# design.net
KiCad netlist of a schematic drawn in Altium Designer
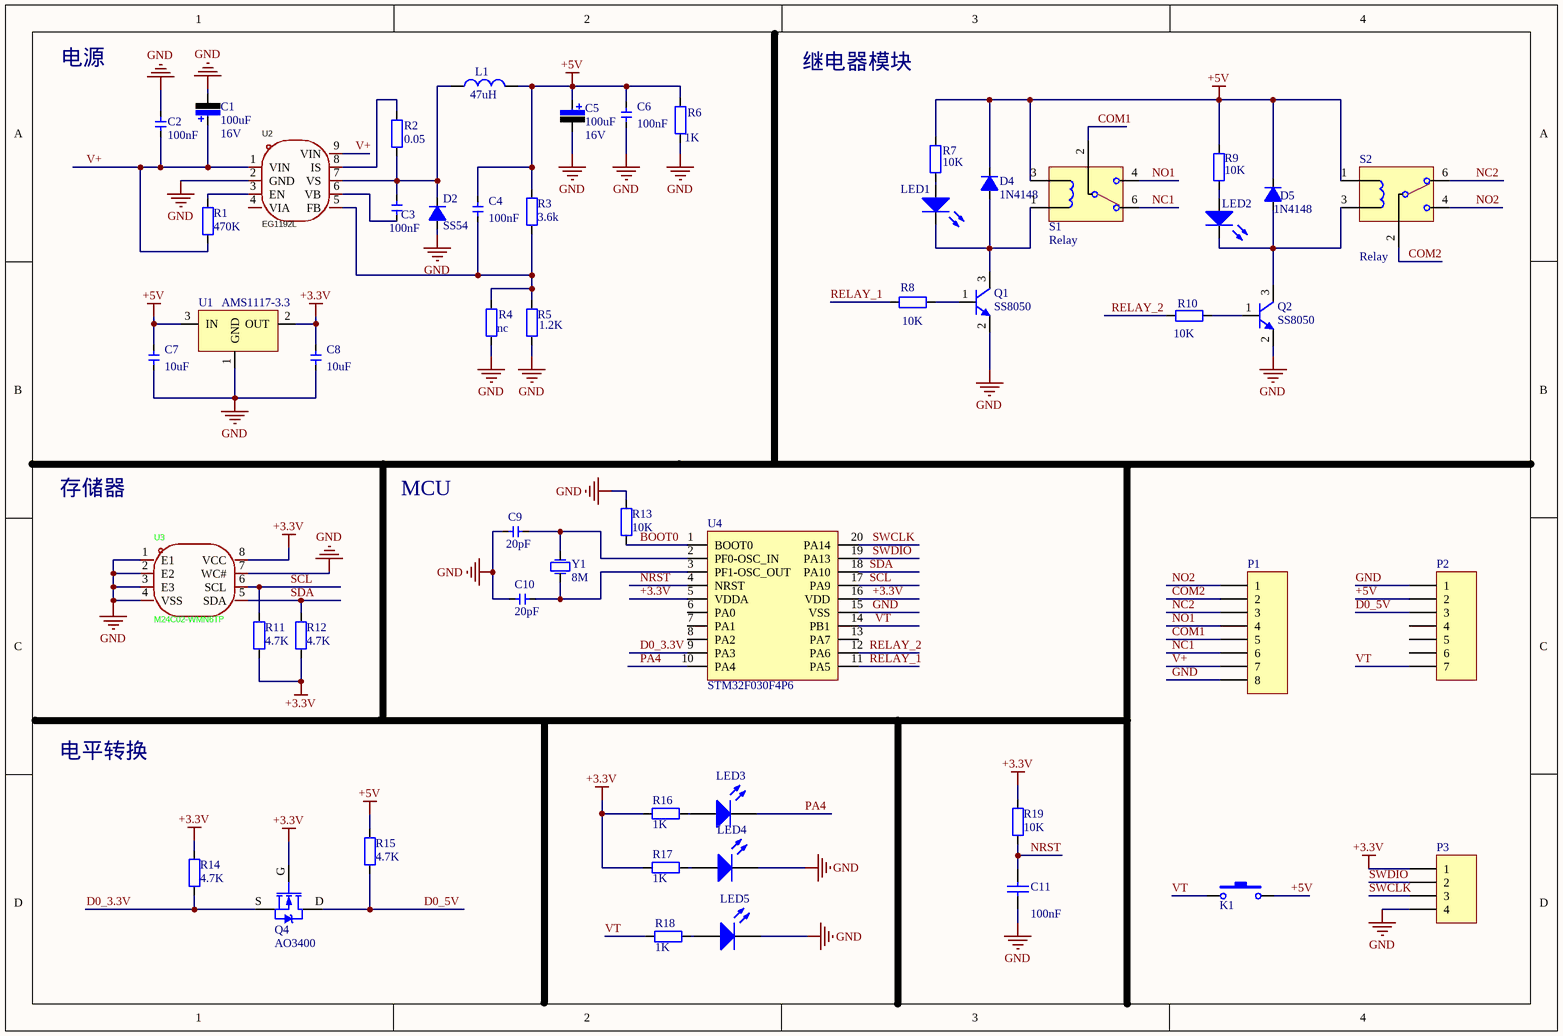
[diagram p0: 遥控启停.SchDoc]

(export (version "E")
  (design (tool "Eeschema 10.0.6"))
  (components
    (comp (ref "C1")
      (value "100uF")
      (footprint "16V100uF")
      (description "极性电解电容")
      (fields
        (field (name "VOL") "16V")
        (field (name "Comment") "Cap Pol")
        (field (name "PUBLISHER") "Altium Limited")
      )
      (libsource (lib "") (part "Cap Pol_1"))
    )
    (comp (ref "C2")
      (value "100nF")
      (footprint "C0603")
      (description "无极性电容")
      (fields (field (name "PUBLISHER") "Altium Limited"))
      (libsource (lib "Arrowy_Racing") (part "Cap"))
    )
    (comp (ref "C3")
      (value "100nF")
      (footprint "C0603")
      (description "无极性电容")
      (fields (field (name "PUBLISHER") "Altium Limited"))
      (libsource (lib "Arrowy_Racing") (part "Cap"))
    )
    (comp (ref "C4")
      (value "100nF")
      (footprint "C0603")
      (description "无极性电容")
      (fields (field (name "PUBLISHER") "Altium Limited"))
      (libsource (lib "Arrowy_Racing") (part "Cap"))
    )
    (comp (ref "C5")
      (value "100uF")
      (footprint "16V100uF")
      (description "极性电解电容")
      (fields
        (field (name "VOL") "16V")
        (field (name "Comment") "Cap Pol")
        (field (name "PUBLISHER") "Altium Limited")
      )
      (libsource (lib "Arrowy_Racing") (part "Cap Pol"))
    )
    (comp (ref "C6")
      (value "100nF")
      (footprint "C0603")
      (description "无极性电容")
      (fields (field (name "PUBLISHER") "Altium Limited"))
      (libsource (lib "Arrowy_Racing") (part "Cap"))
    )
    (comp (ref "C7")
      (value "10uF")
      (footprint "C0603")
      (description "无极性电容")
      (fields (field (name "PUBLISHER") "Altium Limited"))
      (libsource (lib "Arrowy_Racing") (part "Cap"))
    )
    (comp (ref "C8")
      (value "10uF")
      (footprint "C0603")
      (description "无极性电容")
      (fields (field (name "PUBLISHER") "Altium Limited"))
      (libsource (lib "Arrowy_Racing") (part "Cap"))
    )
    (comp (ref "C9")
      (value "20pF")
      (footprint "C0603")
      (description "无极性电容")
      (fields (field (name "PUBLISHER") "Altium Limited"))
      (libsource (lib "Arrowy_Racing") (part "Cap"))
    )
    (comp (ref "C10")
      (value "20pF")
      (footprint "C0603")
      (description "无极性电容")
      (fields (field (name "PUBLISHER") "Altium Limited"))
      (libsource (lib "Arrowy_Racing") (part "Cap"))
    )
    (comp (ref "C11")
      (value "100nF")
      (footprint "C0603")
      (description "Capacitor")
      (fields (field (name "Comment") "0.1uF") (field (name "PUBLISHER") "Altium Limited"))
      (libsource (lib "Miscellaneous Devices") (part "Cap"))
    )
    (comp (ref "D2")
      (value "SS54")
      (footprint "DIODE-SMA")
      (description "二极管")
      (libsource (lib "Arrowy_Racing") (part "Diode"))
    )
    (comp (ref "D4")
      (value "1N4148")
      (footprint "DIODE-1206")
      (description "二极管")
      (libsource (lib "Arrowy_Racing") (part "Diode"))
    )
    (comp (ref "D5")
      (value "1N4148")
      (footprint "DIODE-1206")
      (description "二极管")
      (libsource (lib "Arrowy_Racing") (part "Diode"))
    )
    (comp (ref "K1")
      (value "SW-PB")
      (footprint "SW-SMD_4P-L6.0-W6.0")
      (description "微动开关")
      (fields (field (name "SUPPLITER PART") "C961737") (field (name "PUBLISHER") "Altium Limited"))
      (libsource (lib "Arrowy_Racing") (part "SW-PB"))
    )
    (comp (ref "L1")
      (value "47uH")
      (footprint "IND-SMD_L4.5-W4.0")
      (description "电感")
      (fields (field (name "PUBLISHER") "Altium Limited"))
      (libsource (lib "Arrowy_Racing") (part "Inductor"))
    )
    (comp (ref "LED1")
      (value "LED")
      (footprint "LED0603-RD_RED")
      (description "发光二极管")
      (fields (field (name "PUBLISHER") "Altium Limited"))
      (libsource (lib "Arrowy_Racing") (part "LED"))
    )
    (comp (ref "LED2")
      (value "LED")
      (footprint "LED0603-RD_RED")
      (description "发光二极管")
      (fields (field (name "PUBLISHER") "Altium Limited"))
      (libsource (lib "Arrowy_Racing") (part "LED"))
    )
    (comp (ref "LED3")
      (value "LED0")
      (footprint "LED0603-RD_RED")
      (description "Typical INFRARED GaAs LED")
      (fields (field (name "PUBLISHER") "Altium Limited"))
      (libsource (lib "Miscellaneous Devices") (part "LED0"))
    )
    (comp (ref "LED4")
      (value "LED0")
      (footprint "LED0603-RD_RED")
      (description "Typical INFRARED GaAs LED")
      (fields (field (name "PUBLISHER") "Altium Limited"))
      (libsource (lib "Miscellaneous Devices") (part "LED0"))
    )
    (comp (ref "LED5")
      (value "LED0")
      (footprint "LED0603-RD_RED")
      (description "Typical INFRARED GaAs LED")
      (fields (field (name "PUBLISHER") "Altium Limited"))
      (libsource (lib "Miscellaneous Devices") (part "LED0"))
    )
    (comp (ref "P1")
      (value "Header 8")
      (footprint "XH2.54-W-8P")
      (description "Header, 8-Pin")
      (fields (field (name "PUBLISHER") "Altium Limited"))
      (libsource (lib "Miscellaneous Connectors") (part "Header 8"))
    )
    (comp (ref "P2")
      (value "Header 7")
      (footprint "HDR1X7")
      (description "Header, 7-Pin")
      (fields (field (name "PUBLISHER") "Altium Limited"))
      (libsource (lib "Miscellaneous Connectors") (part "Header 7"))
    )
    (comp (ref "P3")
      (value "Header 4")
      (footprint "HDR1X4")
      (description "Header, 4-Pin")
      (fields (field (name "PUBLISHER") "Altium Limited"))
      (libsource (lib "Miscellaneous Connectors") (part "Header 4"))
    )
    (comp (ref "Q1")
      (value "SS8050")
      (footprint "SOT-23")
      (description "NPN贴片三极管")
      (fields (field (name "PUBLISHER") "Altium Limited"))
      (libsource (lib "Arrowy_Racing") (part "SS8050"))
    )
    (comp (ref "Q2")
      (value "SS8050")
      (footprint "SOT-23")
      (description "NPN贴片三极管")
      (fields (field (name "PUBLISHER") "Altium Limited"))
      (libsource (lib "Arrowy_Racing") (part "SS8050"))
    )
    (comp (ref "Q4")
      (value "AO3400")
      (footprint "SOT-23-MOSFET")
      (description "N沟道MOS管")
      (libsource (lib "Arrowy_Racing") (part "MOSFET-N"))
    )
    (comp (ref "R1")
      (value "470K")
      (footprint "R0603")
      (description "贴片电阻")
      (fields (field (name "PUBLISHER") "Altium Limited"))
      (libsource (lib "Arrowy_Racing") (part "Res"))
    )
    (comp (ref "R2")
      (value "0.05")
      (footprint "R0603")
      (description "贴片电阻")
      (fields (field (name "PUBLISHER") "Altium Limited"))
      (libsource (lib "") (part "Res_2"))
    )
    (comp (ref "R3")
      (value "3.6k")
      (footprint "R0603")
      (description "贴片电阻")
      (fields (field (name "PUBLISHER") "Altium Limited"))
      (libsource (lib "Arrowy_Racing") (part "Res"))
    )
    (comp (ref "R4")
      (value "nc")
      (footprint "R0603")
      (description "贴片电阻")
      (fields (field (name "PUBLISHER") "Altium Limited"))
      (libsource (lib "Arrowy_Racing") (part "Res"))
    )
    (comp (ref "R5")
      (value "1.2K")
      (footprint "R0603")
      (description "贴片电阻")
      (fields (field (name "PUBLISHER") "Altium Limited"))
      (libsource (lib "Arrowy_Racing") (part "Res"))
    )
    (comp (ref "R6")
      (value "1K")
      (footprint "R0603")
      (description "贴片电阻")
      (fields (field (name "PUBLISHER") "Altium Limited"))
      (libsource (lib "Arrowy_Racing") (part "Res"))
    )
    (comp (ref "R7")
      (value "10K")
      (footprint "R0603")
      (description "贴片电阻")
      (fields (field (name "PUBLISHER") "Altium Limited"))
      (libsource (lib "Arrowy_Racing") (part "Res"))
    )
    (comp (ref "R8")
      (value "10K")
      (footprint "R0603")
      (description "贴片电阻")
      (fields (field (name "PUBLISHER") "Altium Limited"))
      (libsource (lib "") (part "Res_1"))
    )
    (comp (ref "R9")
      (value "10K")
      (footprint "R0603")
      (description "贴片电阻")
      (fields (field (name "PUBLISHER") "Altium Limited"))
      (libsource (lib "Arrowy_Racing") (part "Res"))
    )
    (comp (ref "R10")
      (value "10K")
      (footprint "R0603")
      (description "贴片电阻")
      (fields (field (name "PUBLISHER") "Altium Limited"))
      (libsource (lib "") (part "Res_1"))
    )
    (comp (ref "R11")
      (value "4.7K")
      (footprint "R0603")
      (description "贴片电阻")
      (fields (field (name "PUBLISHER") "Altium Limited"))
      (libsource (lib "") (part "Res_2"))
    )
    (comp (ref "R12")
      (value "4.7K")
      (footprint "R0603")
      (description "贴片电阻")
      (fields (field (name "PUBLISHER") "Altium Limited"))
      (libsource (lib "") (part "Res_2"))
    )
    (comp (ref "R13")
      (value "10K")
      (footprint "R0603")
      (description "贴片电阻")
      (fields (field (name "PUBLISHER") "Altium Limited"))
      (libsource (lib "") (part "Res_3"))
    )
    (comp (ref "R14")
      (value "4.7K")
      (footprint "R0603")
      (description "贴片电阻")
      (fields (field (name "PUBLISHER") "Altium Limited"))
      (libsource (lib "Arrowy_Racing") (part "Res"))
    )
    (comp (ref "R15")
      (value "4.7K")
      (footprint "R0603")
      (description "贴片电阻")
      (fields (field (name "PUBLISHER") "Altium Limited"))
      (libsource (lib "Arrowy_Racing") (part "Res"))
    )
    (comp (ref "R16")
      (value "1K")
      (footprint "R0603")
      (description "贴片电阻")
      (fields (field (name "PUBLISHER") "Altium Limited"))
      (libsource (lib "") (part "Res_1"))
    )
    (comp (ref "R17")
      (value "1K")
      (footprint "R0603")
      (description "贴片电阻")
      (fields (field (name "PUBLISHER") "Altium Limited"))
      (libsource (lib "") (part "Res_1"))
    )
    (comp (ref "R18")
      (value "1K")
      (footprint "R0603")
      (description "贴片电阻")
      (fields (field (name "PUBLISHER") "Altium Limited"))
      (libsource (lib "") (part "Res_1"))
    )
    (comp (ref "R19")
      (value "10K")
      (footprint "R0603")
      (description "贴片电阻")
      (fields (field (name "PUBLISHER") "Altium Limited"))
      (libsource (lib "") (part "Res_2"))
    )
    (comp (ref "S1")
      (value "Relay")
      (footprint "SongLe_Relay")
      (description "继电器")
      (libsource (lib "Arrowy_Racing") (part "Relay"))
    )
    (comp (ref "S2")
      (value "Relay")
      (footprint "SongLe_Relay")
      (description "继电器")
      (libsource (lib "") (part "Relay_1"))
    )
    (comp (ref "U1")
      (value "AMS1117-3.3")
      (footprint "SOT89")
      (description "3.3V稳压芯片")
      (libsource (lib "Arrowy_Racing") (part "AMS1117"))
    )
    (comp (ref "U2")
      (value "EG1192L")
      (footprint "ESOP-8_L4.9-W3.9-P1.27-LS6.0-BL-EP")
      (description "10-100V高压电源管理芯片")
      (fields (field (name "MANUFACTURER") "EG(屹晶微)"))
      (libsource (lib "Arrowy_Racing") (part "EG1192L"))
    )
    (comp (ref "U3")
      (value "M24C02-WMN6TP")
      (footprint "SOP-8")
      (fields (field (name "MANUFACTURER") "ST(意法半导体)"))
      (libsource (lib "YAOKONG") (part "M24C02-WMN6TP"))
    )
    (comp (ref "U4")
      (value "STM32F030F4P6")
      (footprint "TSSOP20")
      (description "STM32F030F4P6_CortexM0芯片")
      (libsource (lib "Arrowy_Racing") (part "STM32F030F4P6"))
    )
    (comp (ref "Y1")
      (value "8M")
      (footprint "X-SM49")
      (description "两脚无源晶振")
      (fields (field (name "Comment") "Passive_Crystal_2Pin") (field (name "PUBLISHER") "Altium Limited"))
      (libsource (lib "Arrowy_Racing") (part "Passive_Crystal_2Pin"))
    )
  )
  (nets
    (net (code "1") (name "+3.3V") (class "Default")
      (node (ref "C8") (pin "2") (pinfunction "2_2") (pintype "passive"))
      (node (ref "P3") (pin "1") (pinfunction "1_1") (pintype "passive"))
      (node (ref "Q4") (pin "G") (pinfunction "G_G") (pintype "passive"))
      (node (ref "R11") (pin "2") (pinfunction "2_2") (pintype "passive"))
      (node (ref "R12") (pin "2") (pinfunction "2_2") (pintype "passive"))
      (node (ref "R14") (pin "2") (pinfunction "2_2") (pintype "passive"))
      (node (ref "R16") (pin "2") (pinfunction "2_2") (pintype "passive"))
      (node (ref "R17") (pin "2") (pinfunction "2_2") (pintype "passive"))
      (node (ref "R19") (pin "1") (pinfunction "1_1") (pintype "passive"))
      (node (ref "U1") (pin "2") (pinfunction "OUT_2") (pintype "passive"))
      (node (ref "U3") (pin "8") (pinfunction "VCC_8") (pintype "passive"))
      (node (ref "U4") (pin "16") (pinfunction "VDD_16") (pintype "passive"))
      (node (ref "U4") (pin "5") (pinfunction "VDDA_5") (pintype "passive"))
    )
    (net (code "2") (name "+5V") (class "Default")
      (node (ref "C4") (pin "2") (pinfunction "2_2") (pintype "passive"))
      (node (ref "C5") (pin "1") (pinfunction "1_1") (pintype "passive"))
      (node (ref "C6") (pin "2") (pinfunction "2_2") (pintype "passive"))
      (node (ref "C7") (pin "2") (pinfunction "2_2") (pintype "passive"))
      (node (ref "D4") (pin "2") (pinfunction "K_2") (pintype "passive"))
      (node (ref "D5") (pin "2") (pinfunction "K_2") (pintype "passive"))
      (node (ref "K1") (pin "2") (pinfunction "13_2") (pintype "passive"))
      (node (ref "L1") (pin "2") (pinfunction "2_2") (pintype "passive"))
      (node (ref "P2") (pin "2") (pinfunction "2_2") (pintype "passive"))
      (node (ref "R15") (pin "2") (pinfunction "2_2") (pintype "passive"))
      (node (ref "R3") (pin "2") (pinfunction "2_2") (pintype "passive"))
      (node (ref "R6") (pin "2") (pinfunction "2_2") (pintype "passive"))
      (node (ref "R7") (pin "2") (pinfunction "2_2") (pintype "passive"))
      (node (ref "R9") (pin "2") (pinfunction "2_2") (pintype "passive"))
      (node (ref "S1") (pin "3") (pinfunction "3_3") (pintype "passive"))
      (node (ref "S2") (pin "1") (pinfunction "1_1") (pintype "passive"))
      (node (ref "U1") (pin "3") (pinfunction "IN_3") (pintype "passive"))
    )
    (net (code "3") (name "/BOOT0") (class "Default")
      (node (ref "R13") (pin "1") (pinfunction "1_1") (pintype "passive"))
      (node (ref "U4") (pin "1") (pinfunction "BOOT0_1") (pintype "passive"))
    )
    (net (code "4") (name "/COM1") (class "Default")
      (node (ref "P1") (pin "5") (pinfunction "5_5") (pintype "passive"))
      (node (ref "S1") (pin "2") (pinfunction "2_2") (pintype "passive"))
    )
    (net (code "5") (name "/COM2") (class "Default")
      (node (ref "P1") (pin "2") (pinfunction "2_2") (pintype "passive"))
      (node (ref "S2") (pin "2") (pinfunction "2_2") (pintype "passive"))
    )
    (net (code "6") (name "/D0_3.3V") (class "Default")
      (node (ref "Q4") (pin "S") (pinfunction "S_S") (pintype "passive"))
      (node (ref "R14") (pin "1") (pinfunction "1_1") (pintype "passive"))
      (node (ref "U4") (pin "9") (pinfunction "PA3_9") (pintype "passive"))
    )
    (net (code "7") (name "/D0_5V") (class "Default")
      (node (ref "P2") (pin "3") (pinfunction "3_3") (pintype "passive"))
      (node (ref "Q4") (pin "D") (pinfunction "D_D") (pintype "passive"))
      (node (ref "R15") (pin "1") (pinfunction "1_1") (pintype "passive"))
    )
    (net (code "8") (name "/NC1") (class "Default")
      (node (ref "P1") (pin "6") (pinfunction "6_6") (pintype "passive"))
      (node (ref "S1") (pin "6") (pinfunction "6_6") (pintype "passive"))
    )
    (net (code "9") (name "/NC2") (class "Default")
      (node (ref "P1") (pin "3") (pinfunction "3_3") (pintype "passive"))
      (node (ref "S2") (pin "6") (pinfunction "6_6") (pintype "passive"))
    )
    (net (code "10") (name "/NO1") (class "Default")
      (node (ref "P1") (pin "4") (pinfunction "4_4") (pintype "passive"))
      (node (ref "S1") (pin "4") (pinfunction "4_4") (pintype "passive"))
    )
    (net (code "11") (name "/NO2") (class "Default")
      (node (ref "P1") (pin "1") (pinfunction "1_1") (pintype "passive"))
      (node (ref "S2") (pin "4") (pinfunction "4_4") (pintype "passive"))
    )
    (net (code "12") (name "/NRST") (class "Default")
      (node (ref "C11") (pin "2") (pinfunction "2_2") (pintype "passive"))
      (node (ref "R19") (pin "2") (pinfunction "2_2") (pintype "passive"))
      (node (ref "U4") (pin "4") (pinfunction "NRST_4") (pintype "passive"))
    )
    (net (code "13") (name "/PA4") (class "Default")
      (node (ref "LED3") (pin "2") (pinfunction "K_2") (pintype "passive"))
      (node (ref "U4") (pin "10") (pinfunction "PA4_10") (pintype "passive"))
    )
    (net (code "14") (name "/RELAY_1") (class "Default")
      (node (ref "R8") (pin "2") (pinfunction "2_2") (pintype "passive"))
      (node (ref "U4") (pin "11") (pinfunction "PA5_11") (pintype "passive"))
    )
    (net (code "15") (name "/RELAY_2") (class "Default")
      (node (ref "R10") (pin "2") (pinfunction "2_2") (pintype "passive"))
      (node (ref "U4") (pin "12") (pinfunction "PA6_12") (pintype "passive"))
    )
    (net (code "16") (name "/SCL") (class "Default")
      (node (ref "R11") (pin "1") (pinfunction "1_1") (pintype "passive"))
      (node (ref "U3") (pin "6") (pinfunction "SCL_6") (pintype "passive"))
      (node (ref "U4") (pin "17") (pinfunction "PA9_17") (pintype "passive"))
    )
    (net (code "17") (name "/SDA") (class "Default")
      (node (ref "R12") (pin "1") (pinfunction "1_1") (pintype "passive"))
      (node (ref "U3") (pin "5") (pinfunction "SDA_5") (pintype "passive"))
      (node (ref "U4") (pin "18") (pinfunction "PA10_18") (pintype "passive"))
    )
    (net (code "18") (name "/SWCLK") (class "Default")
      (node (ref "P3") (pin "3") (pinfunction "3_3") (pintype "passive"))
      (node (ref "U4") (pin "20") (pinfunction "PA14_20") (pintype "passive"))
    )
    (net (code "19") (name "/SWDIO") (class "Default")
      (node (ref "P3") (pin "2") (pinfunction "2_2") (pintype "passive"))
      (node (ref "U4") (pin "19") (pinfunction "PA13_19") (pintype "passive"))
    )
    (net (code "20") (name "/V+") (class "Default")
      (node (ref "C1") (pin "1") (pinfunction "1_1") (pintype "passive"))
      (node (ref "C2") (pin "1") (pinfunction "1_1") (pintype "passive"))
      (node (ref "P1") (pin "7") (pinfunction "7_7") (pintype "passive"))
      (node (ref "R1") (pin "1") (pinfunction "1_1") (pintype "passive"))
      (node (ref "U2") (pin "1") (pinfunction "VIN_1") (pintype "passive"))
      (node (ref "U2") (pin "9") (pinfunction "VIN_9") (pintype "passive"))
    )
    (net (code "21") (name "/VT") (class "Default")
      (node (ref "K1") (pin "1") (pinfunction "1_1") (pintype "passive"))
      (node (ref "P2") (pin "7") (pinfunction "7_7") (pintype "passive"))
      (node (ref "R18") (pin "2") (pinfunction "2_2") (pintype "passive"))
      (node (ref "U4") (pin "14") (pinfunction "PB1_14") (pintype "passive"))
    )
    (net (code "22") (name "GND") (class "Default")
      (node (ref "C1") (pin "2") (pinfunction "2_2") (pintype "passive"))
      (node (ref "C10") (pin "2") (pinfunction "2_2") (pintype "passive"))
      (node (ref "C11") (pin "1") (pinfunction "1_1") (pintype "passive"))
      (node (ref "C2") (pin "2") (pinfunction "2_2") (pintype "passive"))
      (node (ref "C5") (pin "2") (pinfunction "2_2") (pintype "passive"))
      (node (ref "C6") (pin "1") (pinfunction "1_1") (pintype "passive"))
      (node (ref "C7") (pin "1") (pinfunction "1_1") (pintype "passive"))
      (node (ref "C8") (pin "1") (pinfunction "1_1") (pintype "passive"))
      (node (ref "C9") (pin "2") (pinfunction "2_2") (pintype "passive"))
      (node (ref "D2") (pin "1") (pinfunction "A_1") (pintype "passive"))
      (node (ref "LED4") (pin "2") (pinfunction "K_2") (pintype "passive"))
      (node (ref "LED5") (pin "2") (pinfunction "K_2") (pintype "passive"))
      (node (ref "P1") (pin "8") (pinfunction "8_8") (pintype "passive"))
      (node (ref "P2") (pin "1") (pinfunction "1_1") (pintype "passive"))
      (node (ref "P3") (pin "4") (pinfunction "4_4") (pintype "passive"))
      (node (ref "Q1") (pin "2") (pinfunction "E_2") (pintype "passive"))
      (node (ref "Q2") (pin "2") (pinfunction "E_2") (pintype "passive"))
      (node (ref "R13") (pin "2") (pinfunction "2_2") (pintype "passive"))
      (node (ref "R4") (pin "1") (pinfunction "1_1") (pintype "passive"))
      (node (ref "R5") (pin "1") (pinfunction "1_1") (pintype "passive"))
      (node (ref "R6") (pin "1") (pinfunction "1_1") (pintype "passive"))
      (node (ref "U1") (pin "1") (pinfunction "GND_1") (pintype "passive"))
      (node (ref "U2") (pin "2") (pinfunction "GND_2") (pintype "passive"))
      (node (ref "U3") (pin "1") (pinfunction "E1_1") (pintype "passive"))
      (node (ref "U3") (pin "2") (pinfunction "E2_2") (pintype "passive"))
      (node (ref "U3") (pin "3") (pinfunction "E3_3") (pintype "passive"))
      (node (ref "U3") (pin "4") (pinfunction "VSS_4") (pintype "passive"))
      (node (ref "U3") (pin "7") (pinfunction "WC#_7") (pintype "passive"))
      (node (ref "U4") (pin "15") (pinfunction "VSS_15") (pintype "passive"))
    )
    (net (code "23") (name "Net-(D2-K)") (class "Default")
      (node (ref "C3") (pin "2") (pinfunction "2_2") (pintype "passive"))
      (node (ref "D2") (pin "2") (pinfunction "K_2") (pintype "passive"))
      (node (ref "L1") (pin "1") (pinfunction "1_1") (pintype "passive"))
      (node (ref "R2") (pin "2") (pinfunction "2_2") (pintype "passive"))
      (node (ref "U2") (pin "7") (pinfunction "VS_7") (pintype "passive"))
    )
    (net (code "24") (name "Net-(D4-A)") (class "Default")
      (node (ref "D4") (pin "1") (pinfunction "A_1") (pintype "passive"))
      (node (ref "LED1") (pin "2") (pinfunction "K_2") (pintype "passive"))
      (node (ref "Q1") (pin "3") (pinfunction "C_3") (pintype "passive"))
      (node (ref "S1") (pin "1") (pinfunction "1_1") (pintype "passive"))
    )
    (net (code "25") (name "Net-(D5-A)") (class "Default")
      (node (ref "D5") (pin "1") (pinfunction "A_1") (pintype "passive"))
      (node (ref "LED2") (pin "2") (pinfunction "K_2") (pintype "passive"))
      (node (ref "Q2") (pin "3") (pinfunction "C_3") (pintype "passive"))
      (node (ref "S2") (pin "3") (pinfunction "3_3") (pintype "passive"))
    )
    (net (code "26") (name "Net-(LED1-A)") (class "Default")
      (node (ref "LED1") (pin "1") (pinfunction "A_1") (pintype "passive"))
      (node (ref "R7") (pin "1") (pinfunction "1_1") (pintype "passive"))
    )
    (net (code "27") (name "Net-(LED2-A)") (class "Default")
      (node (ref "LED2") (pin "1") (pinfunction "A_1") (pintype "passive"))
      (node (ref "R9") (pin "1") (pinfunction "1_1") (pintype "passive"))
    )
    (net (code "28") (name "Net-(LED3-A)") (class "Default")
      (node (ref "LED3") (pin "1") (pinfunction "A_1") (pintype "passive"))
      (node (ref "R16") (pin "1") (pinfunction "1_1") (pintype "passive"))
    )
    (net (code "29") (name "Net-(LED4-A)") (class "Default")
      (node (ref "LED4") (pin "1") (pinfunction "A_1") (pintype "passive"))
      (node (ref "R17") (pin "1") (pinfunction "1_1") (pintype "passive"))
    )
    (net (code "30") (name "Net-(LED5-A)") (class "Default")
      (node (ref "LED5") (pin "1") (pinfunction "A_1") (pintype "passive"))
      (node (ref "R18") (pin "1") (pinfunction "1_1") (pintype "passive"))
    )
    (net (code "31") (name "Net-(Q1-B)") (class "Default")
      (node (ref "Q1") (pin "1") (pinfunction "B_1") (pintype "passive"))
      (node (ref "R8") (pin "1") (pinfunction "1_1") (pintype "passive"))
    )
    (net (code "32") (name "Net-(Q2-B)") (class "Default")
      (node (ref "Q2") (pin "1") (pinfunction "B_1") (pintype "passive"))
      (node (ref "R10") (pin "1") (pinfunction "1_1") (pintype "passive"))
    )
    (net (code "33") (name "Net-(U2-EN)") (class "Default")
      (node (ref "R1") (pin "2") (pinfunction "2_2") (pintype "passive"))
      (node (ref "U2") (pin "3") (pinfunction "EN_3") (pintype "passive"))
    )
    (net (code "34") (name "Net-(U2-FB)") (class "Default")
      (node (ref "C4") (pin "1") (pinfunction "1_1") (pintype "passive"))
      (node (ref "R3") (pin "1") (pinfunction "1_1") (pintype "passive"))
      (node (ref "R4") (pin "2") (pinfunction "2_2") (pintype "passive"))
      (node (ref "R5") (pin "2") (pinfunction "2_2") (pintype "passive"))
      (node (ref "U2") (pin "5") (pinfunction "FB_5") (pintype "passive"))
    )
    (net (code "35") (name "Net-(U2-IS)") (class "Default")
      (node (ref "R2") (pin "1") (pinfunction "1_1") (pintype "passive"))
      (node (ref "U2") (pin "8") (pinfunction "IS_8") (pintype "passive"))
    )
    (net (code "36") (name "Net-(U2-VB)") (class "Default")
      (node (ref "C3") (pin "1") (pinfunction "1_1") (pintype "passive"))
      (node (ref "U2") (pin "6") (pinfunction "VB_6") (pintype "passive"))
    )
    (net (code "37") (name "Net-(U4-PF0-OSC_IN)") (class "Default")
      (node (ref "C9") (pin "1") (pinfunction "1_1") (pintype "passive"))
      (node (ref "U4") (pin "2") (pinfunction "PF0-OSC_IN_2") (pintype "passive"))
      (node (ref "Y1") (pin "1") (pinfunction "1_1") (pintype "passive"))
    )
    (net (code "38") (name "Net-(U4-PF1-OSC_OUT)") (class "Default")
      (node (ref "C10") (pin "1") (pinfunction "1_1") (pintype "passive"))
      (node (ref "U4") (pin "3") (pinfunction "PF1-OSC_OUT_3") (pintype "passive"))
      (node (ref "Y1") (pin "2") (pinfunction "2_2") (pintype "passive"))
    )
    (net (code "39") (name "unconnected-(P2-Pad4)") (class "Default")
      (node (ref "P2") (pin "4") (pinfunction "4_4") (pintype "passive"))
    )
    (net (code "40") (name "unconnected-(P2-Pad5)") (class "Default")
      (node (ref "P2") (pin "5") (pinfunction "5_5") (pintype "passive"))
    )
    (net (code "41") (name "unconnected-(P2-Pad6)") (class "Default")
      (node (ref "P2") (pin "6") (pinfunction "6_6") (pintype "passive"))
    )
    (net (code "42") (name "unconnected-(U2-VIA-Pad4)") (class "Default")
      (node (ref "U2") (pin "4") (pinfunction "VIA_4") (pintype "passive"))
    )
    (net (code "43") (name "unconnected-(U4-PA0-Pad6)") (class "Default")
      (node (ref "U4") (pin "6") (pinfunction "PA0_6") (pintype "passive"))
    )
    (net (code "44") (name "unconnected-(U4-PA1-Pad7)") (class "Default")
      (node (ref "U4") (pin "7") (pinfunction "PA1_7") (pintype "passive"))
    )
    (net (code "45") (name "unconnected-(U4-PA2-Pad8)") (class "Default")
      (node (ref "U4") (pin "8") (pinfunction "PA2_8") (pintype "passive"))
    )
    (net (code "46") (name "unconnected-(U4-PA7-Pad13)") (class "Default")
      (node (ref "U4") (pin "13") (pinfunction "PA7_13") (pintype "passive"))
    )
  )
)
